# USB.net
KiCad netlist of a schematic drawn in Altium Designer
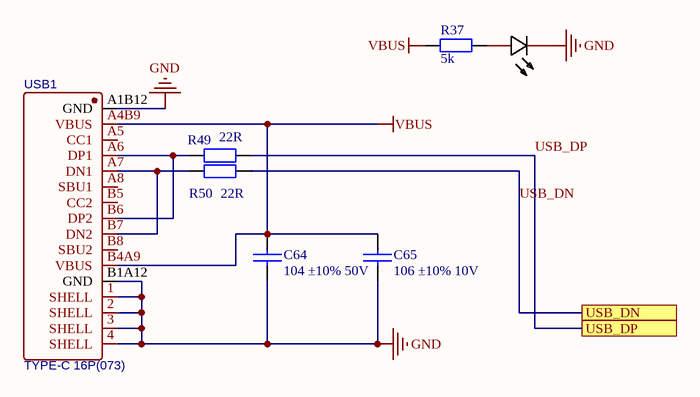
[diagram p0: USB.SchDoc]

(export (version "E")
  (design (tool "Eeschema 10.0.6"))
  (components
    (comp (ref "5")
      (value "NCD0603R1_C84263")
      (footprint "0603LED")
      (fields (field (name "MANUFACTURER") "国星光电") (field (name "MANUFACTURER PART") "NCD0603R1"))
      (libsource (lib "FOC") (part "0603LED"))
    )
    (comp (ref "C64")
      (value "104 ±10% 50V")
      (footprint "0402C")
      (description "Capacitor")
      (libsource (lib "Y常用") (part "Cap"))
    )
    (comp (ref "C65")
      (value "106 ±10% 10V")
      (footprint "0402C")
      (description "Capacitor")
      (libsource (lib "Y常用") (part "Cap"))
    )
    (comp (ref "R37")
      (value "5k")
      (footprint "0402R")
      (description "Resistor")
      (fields (field (name "PUBLISHER") "Altium Limited"))
      (libsource (lib "Miscellaneous Devices") (part "Res2"))
    )
    (comp (ref "R49")
      (value "22R")
      (footprint "0402R")
      (description "贴片电阻")
      (libsource (lib "FOC") (part "RES"))
    )
    (comp (ref "R50")
      (value "22R")
      (footprint "0402R")
      (description "贴片电阻")
      (libsource (lib "FOC") (part "RES"))
    )
    (comp (ref "USB1")
      (value "TYPE-C 16P(073)")
      (footprint "USB-C-SMD_16P - duplicate2")
      (fields (field (name "BOM_SUPPLIER PART") "C668624") (field (name "CONTRIBUTOR") "LCSC"))
      (libsource (lib "FOC") (part "TYPE-C 16P(073)"))
    )
  )
  (nets
    (net (code "1") (name "/USB_DN") (class "Default")
      (node (ref "R50") (pin "1") (pinfunction "1_1") (pintype "passive"))
    )
    (net (code "2") (name "/USB_DP") (class "Default")
      (node (ref "R49") (pin "1") (pinfunction "1_1") (pintype "passive"))
    )
    (net (code "3") (name "GND") (class "Default")
      (node (ref "5") (pin "1") (pinfunction "K_1") (pintype "passive"))
      (node (ref "C64") (pin "1") (pintype "passive"))
      (node (ref "C65") (pin "1") (pintype "passive"))
      (node (ref "USB1") (pin "1") (pinfunction "SHELL_1") (pintype "passive"))
      (node (ref "USB1") (pin "2") (pinfunction "SHELL_2") (pintype "passive"))
      (node (ref "USB1") (pin "3") (pinfunction "SHELL_3") (pintype "passive"))
      (node (ref "USB1") (pin "4") (pinfunction "SHELL_4") (pintype "passive"))
      (node (ref "USB1") (pin "A1B12") (pinfunction "GND_A1B12") (pintype "passive"))
      (node (ref "USB1") (pin "B1A12") (pinfunction "GND_B1A12") (pintype "passive"))
    )
    (net (code "4") (name "Net-(5-A)") (class "Default")
      (node (ref "5") (pin "2") (pinfunction "A_2") (pintype "passive"))
      (node (ref "R37") (pin "2") (pinfunction "2_2") (pintype "passive"))
    )
    (net (code "5") (name "Net-(USB1-DN1)") (class "Default")
      (node (ref "R50") (pin "2") (pinfunction "2_2") (pintype "passive"))
      (node (ref "USB1") (pin "A7") (pinfunction "DN1_A7") (pintype "passive"))
      (node (ref "USB1") (pin "B7") (pinfunction "DN2_B7") (pintype "passive"))
    )
    (net (code "6") (name "Net-(USB1-DP1)") (class "Default")
      (node (ref "R49") (pin "2") (pinfunction "2_2") (pintype "passive"))
      (node (ref "USB1") (pin "A6") (pinfunction "DP1_A6") (pintype "passive"))
      (node (ref "USB1") (pin "B6") (pinfunction "DP2_B6") (pintype "passive"))
    )
    (net (code "7") (name "VBUS") (class "Default")
      (node (ref "C64") (pin "2") (pintype "passive"))
      (node (ref "C65") (pin "2") (pintype "passive"))
      (node (ref "R37") (pin "1") (pinfunction "1_1") (pintype "passive"))
      (node (ref "USB1") (pin "A4B9") (pinfunction "VBUS_A4B9") (pintype "passive"))
      (node (ref "USB1") (pin "B4A9") (pinfunction "VBUS_B4A9") (pintype "passive"))
    )
    (net (code "8") (name "unconnected-(USB1-CC1-PadA5)") (class "Default")
      (node (ref "USB1") (pin "A5") (pinfunction "CC1_A5") (pintype "passive"))
    )
    (net (code "9") (name "unconnected-(USB1-CC2-PadB5)") (class "Default")
      (node (ref "USB1") (pin "B5") (pinfunction "CC2_B5") (pintype "passive"))
    )
    (net (code "10") (name "unconnected-(USB1-SBU1-PadA8)") (class "Default")
      (node (ref "USB1") (pin "A8") (pinfunction "SBU1_A8") (pintype "passive"))
    )
    (net (code "11") (name "unconnected-(USB1-SBU2-PadB8)") (class "Default")
      (node (ref "USB1") (pin "B8") (pinfunction "SBU2_B8") (pintype "passive"))
    )
  )
)
